# SCH_Club-Vote-Decider_2025-12-05_1.net
KiCad netlist of a schematic drawn in EasyEDA
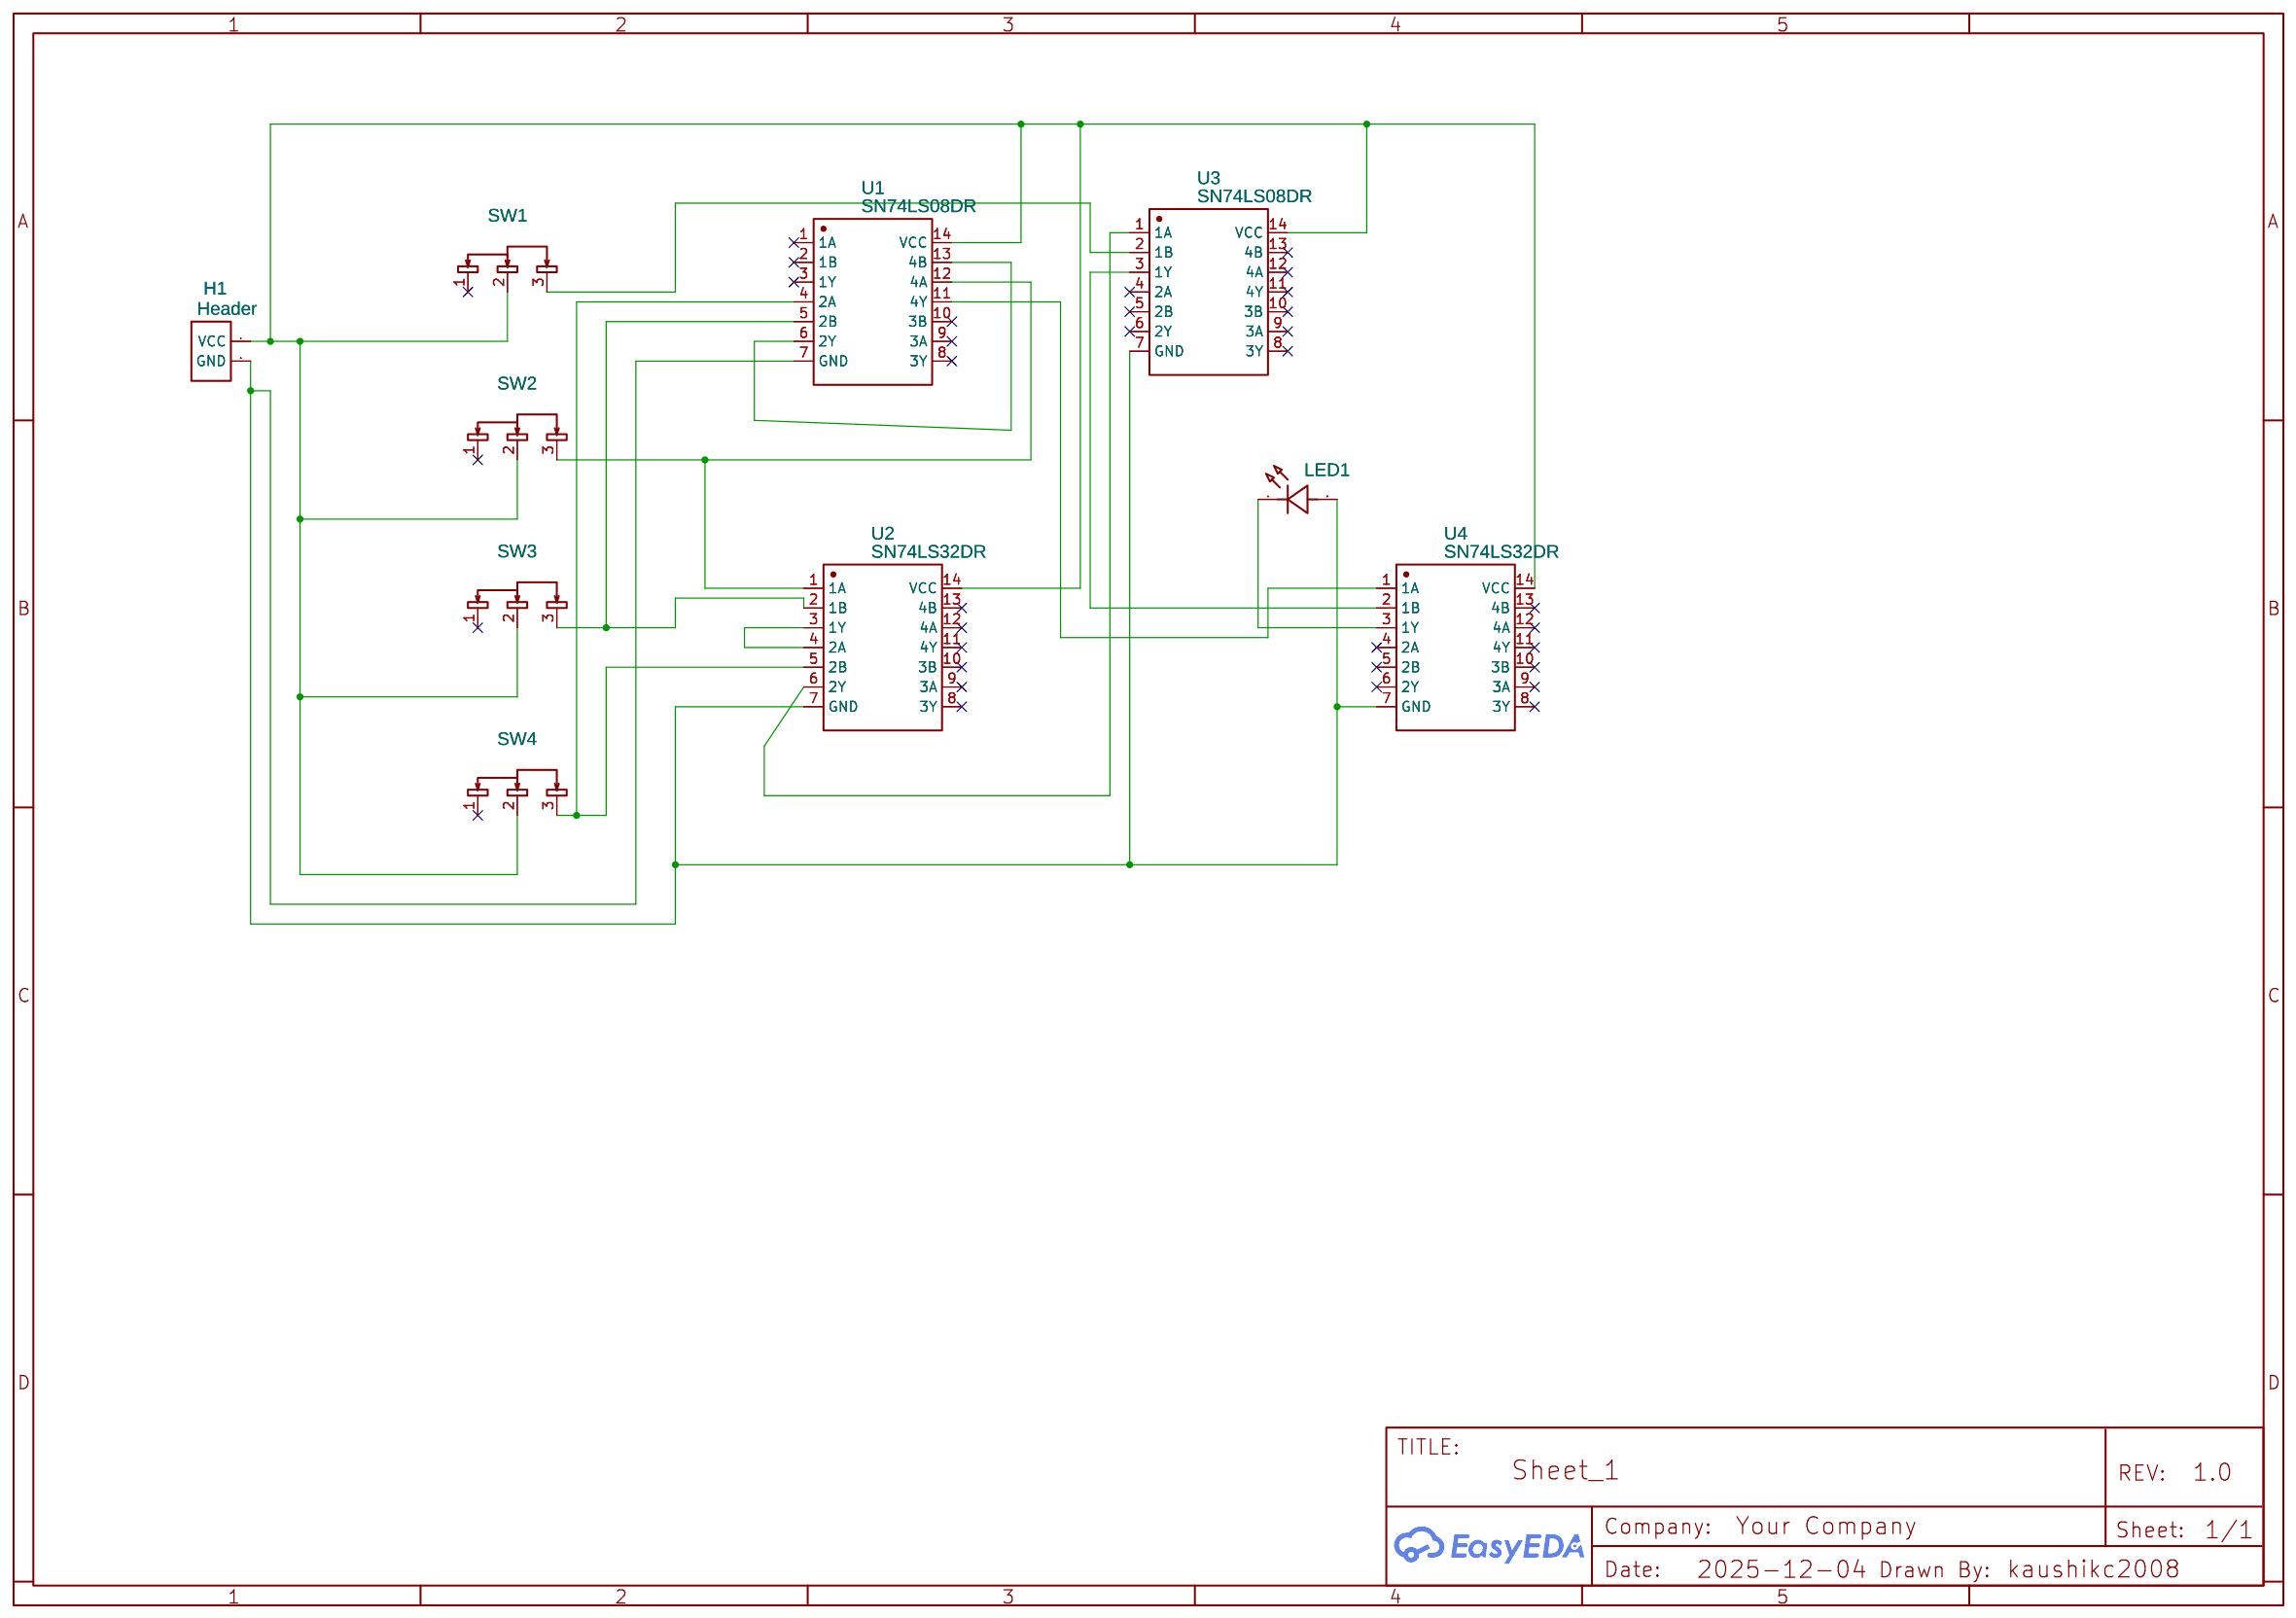
[diagram p0: schematic sheet]

(export (version "E")
  (design (tool "Eeschema 10.0.6"))
  (components
    (comp (ref "H1") (value "Header") (libsource (lib "") (part "HEADER-FEMALE-2.54_1X2")))
    (comp (ref "LED1")
      (value "XL-502UWC")
      (fields (field (name "Manufacturer") "XINGLIGHT(成兴光)"))
      (libsource (lib "") (part "XL-502UWC"))
    )
    (comp (ref "SW1")
      (value "MST-12D18G4 SPDT SLIDE SWITCH")
      (fields
        (field (name "Manufacturer Part") "MST-12D18G4 SPDT Slide Switch")
        (field (name "Manufacturer") "SHOU HAN(首韩)")
      )
      (libsource (lib "") (part "MST-12D18G4 SPDT SLIDE SWITCH"))
    )
    (comp (ref "SW2")
      (value "MST-12D18G4 SPDT SLIDE SWITCH")
      (fields
        (field (name "Manufacturer Part") "MST-12D18G4 SPDT Slide Switch")
        (field (name "Manufacturer") "SHOU HAN(首韩)")
      )
      (libsource (lib "") (part "MST-12D18G4 SPDT SLIDE SWITCH"))
    )
    (comp (ref "SW3")
      (value "MST-12D18G4 SPDT SLIDE SWITCH")
      (fields
        (field (name "Manufacturer Part") "MST-12D18G4 SPDT Slide Switch")
        (field (name "Manufacturer") "SHOU HAN(首韩)")
      )
      (libsource (lib "") (part "MST-12D18G4 SPDT SLIDE SWITCH"))
    )
    (comp (ref "SW4")
      (value "MST-12D18G4 SPDT SLIDE SWITCH")
      (fields
        (field (name "Manufacturer Part") "MST-12D18G4 SPDT Slide Switch")
        (field (name "Manufacturer") "SHOU HAN(首韩)")
      )
      (libsource (lib "") (part "MST-12D18G4 SPDT SLIDE SWITCH"))
    )
    (comp (ref "U1")
      (value "SN74LS08DR")
      (fields (field (name "Manufacturer") "TI(德州仪器)"))
      (libsource (lib "") (part "SN74LS08DR"))
    )
    (comp (ref "U2")
      (value "SN74LS32DR")
      (fields (field (name "Manufacturer") "TI(德州仪器)"))
      (libsource (lib "") (part "SN74LS32DR"))
    )
    (comp (ref "U3")
      (value "SN74LS08DR")
      (fields (field (name "Manufacturer") "TI(德州仪器)"))
      (libsource (lib "") (part "SN74LS08DR"))
    )
    (comp (ref "U4")
      (value "SN74LS32DR")
      (fields (field (name "Manufacturer") "TI(德州仪器)"))
      (libsource (lib "") (part "SN74LS32DR"))
    )
  )
  (nets
    (net (code "1") (name "Net-(H1-GND)") (class "Default")
      (node (ref "H1") (pin "2") (pinfunction "GND_2") (pintype "unspecified"))
      (node (ref "LED1") (pin "2") (pinfunction "A_2") (pintype "unspecified"))
      (node (ref "U1") (pin "7") (pinfunction "GND_7") (pintype "unspecified"))
      (node (ref "U2") (pin "7") (pinfunction "GND_7") (pintype "unspecified"))
      (node (ref "U3") (pin "7") (pinfunction "GND_7") (pintype "unspecified"))
      (node (ref "U4") (pin "7") (pinfunction "GND_7") (pintype "unspecified"))
    )
    (net (code "2") (name "Net-(H1-VCC)") (class "Default")
      (node (ref "H1") (pin "1") (pinfunction "VCC_1") (pintype "unspecified"))
      (node (ref "SW1") (pin "2") (pinfunction "2_2") (pintype "unspecified"))
      (node (ref "SW2") (pin "2") (pinfunction "2_2") (pintype "unspecified"))
      (node (ref "SW3") (pin "2") (pinfunction "2_2") (pintype "unspecified"))
      (node (ref "SW4") (pin "2") (pinfunction "2_2") (pintype "unspecified"))
      (node (ref "U1") (pin "14") (pinfunction "VCC_14") (pintype "unspecified"))
      (node (ref "U2") (pin "14") (pinfunction "VCC_14") (pintype "unspecified"))
      (node (ref "U3") (pin "14") (pinfunction "VCC_14") (pintype "unspecified"))
      (node (ref "U4") (pin "14") (pinfunction "VCC_14") (pintype "unspecified"))
    )
    (net (code "3") (name "Net-(LED1-K)") (class "Default")
      (node (ref "LED1") (pin "1") (pinfunction "K_1") (pintype "unspecified"))
      (node (ref "U4") (pin "3") (pinfunction "1Y_3") (pintype "unspecified"))
    )
    (net (code "4") (name "Net-(U1-2A)") (class "Default")
      (node (ref "SW4") (pin "3") (pinfunction "3_3") (pintype "unspecified"))
      (node (ref "U1") (pin "4") (pinfunction "2A_4") (pintype "unspecified"))
      (node (ref "U2") (pin "5") (pinfunction "2B_5") (pintype "unspecified"))
    )
    (net (code "5") (name "Net-(U1-2B)") (class "Default")
      (node (ref "SW3") (pin "3") (pinfunction "3_3") (pintype "unspecified"))
      (node (ref "U1") (pin "5") (pinfunction "2B_5") (pintype "unspecified"))
      (node (ref "U2") (pin "2") (pinfunction "1B_2") (pintype "unspecified"))
    )
    (net (code "6") (name "Net-(U1-2Y)") (class "Default")
      (node (ref "U1") (pin "13") (pinfunction "4B_13") (pintype "unspecified"))
      (node (ref "U1") (pin "6") (pinfunction "2Y_6") (pintype "unspecified"))
    )
    (net (code "7") (name "Net-(U1-4A)") (class "Default")
      (node (ref "SW2") (pin "3") (pinfunction "3_3") (pintype "unspecified"))
      (node (ref "U1") (pin "12") (pinfunction "4A_12") (pintype "unspecified"))
      (node (ref "U2") (pin "1") (pinfunction "1A_1") (pintype "unspecified"))
    )
    (net (code "8") (name "Net-(U1-4Y)") (class "Default")
      (node (ref "U1") (pin "11") (pinfunction "4Y_11") (pintype "unspecified"))
      (node (ref "U4") (pin "1") (pinfunction "1A_1") (pintype "unspecified"))
    )
    (net (code "9") (name "Net-(U2-1Y)") (class "Default")
      (node (ref "U2") (pin "3") (pinfunction "1Y_3") (pintype "unspecified"))
      (node (ref "U2") (pin "4") (pinfunction "2A_4") (pintype "unspecified"))
    )
    (net (code "10") (name "Net-(U2-2Y)") (class "Default")
      (node (ref "U2") (pin "6") (pinfunction "2Y_6") (pintype "unspecified"))
      (node (ref "U3") (pin "1") (pinfunction "1A_1") (pintype "unspecified"))
    )
    (net (code "11") (name "Net-(U3-1B)") (class "Default")
      (node (ref "SW1") (pin "3") (pinfunction "3_3") (pintype "unspecified"))
      (node (ref "U3") (pin "2") (pinfunction "1B_2") (pintype "unspecified"))
    )
    (net (code "12") (name "Net-(U3-1Y)") (class "Default")
      (node (ref "U3") (pin "3") (pinfunction "1Y_3") (pintype "unspecified"))
      (node (ref "U4") (pin "2") (pinfunction "1B_2") (pintype "unspecified"))
    )
    (net (code "13") (name "unconnected-(SW1-Pad1)") (class "Default")
      (node (ref "SW1") (pin "1") (pinfunction "1_1") (pintype "unspecified+no_connect"))
    )
    (net (code "14") (name "unconnected-(SW2-Pad1)") (class "Default")
      (node (ref "SW2") (pin "1") (pinfunction "1_1") (pintype "unspecified+no_connect"))
    )
    (net (code "15") (name "unconnected-(SW3-Pad1)") (class "Default")
      (node (ref "SW3") (pin "1") (pinfunction "1_1") (pintype "unspecified+no_connect"))
    )
    (net (code "16") (name "unconnected-(SW4-Pad1)") (class "Default")
      (node (ref "SW4") (pin "1") (pinfunction "1_1") (pintype "unspecified+no_connect"))
    )
    (net (code "17") (name "unconnected-(U1-1A-Pad1)") (class "Default")
      (node (ref "U1") (pin "1") (pinfunction "1A_1") (pintype "unspecified+no_connect"))
    )
    (net (code "18") (name "unconnected-(U1-1B-Pad2)") (class "Default")
      (node (ref "U1") (pin "2") (pinfunction "1B_2") (pintype "unspecified+no_connect"))
    )
    (net (code "19") (name "unconnected-(U1-1Y-Pad3)") (class "Default")
      (node (ref "U1") (pin "3") (pinfunction "1Y_3") (pintype "unspecified+no_connect"))
    )
    (net (code "20") (name "unconnected-(U1-3A-Pad9)") (class "Default")
      (node (ref "U1") (pin "9") (pinfunction "3A_9") (pintype "unspecified+no_connect"))
    )
    (net (code "21") (name "unconnected-(U1-3B-Pad10)") (class "Default")
      (node (ref "U1") (pin "10") (pinfunction "3B_10") (pintype "unspecified+no_connect"))
    )
    (net (code "22") (name "unconnected-(U1-3Y-Pad8)") (class "Default")
      (node (ref "U1") (pin "8") (pinfunction "3Y_8") (pintype "unspecified+no_connect"))
    )
    (net (code "23") (name "unconnected-(U2-3A-Pad9)") (class "Default")
      (node (ref "U2") (pin "9") (pinfunction "3A_9") (pintype "unspecified+no_connect"))
    )
    (net (code "24") (name "unconnected-(U2-3B-Pad10)") (class "Default")
      (node (ref "U2") (pin "10") (pinfunction "3B_10") (pintype "unspecified+no_connect"))
    )
    (net (code "25") (name "unconnected-(U2-3Y-Pad8)") (class "Default")
      (node (ref "U2") (pin "8") (pinfunction "3Y_8") (pintype "unspecified+no_connect"))
    )
    (net (code "26") (name "unconnected-(U2-4A-Pad12)") (class "Default")
      (node (ref "U2") (pin "12") (pinfunction "4A_12") (pintype "unspecified+no_connect"))
    )
    (net (code "27") (name "unconnected-(U2-4B-Pad13)") (class "Default")
      (node (ref "U2") (pin "13") (pinfunction "4B_13") (pintype "unspecified+no_connect"))
    )
    (net (code "28") (name "unconnected-(U2-4Y-Pad11)") (class "Default")
      (node (ref "U2") (pin "11") (pinfunction "4Y_11") (pintype "unspecified+no_connect"))
    )
    (net (code "29") (name "unconnected-(U3-2A-Pad4)") (class "Default")
      (node (ref "U3") (pin "4") (pinfunction "2A_4") (pintype "unspecified+no_connect"))
    )
    (net (code "30") (name "unconnected-(U3-2B-Pad5)") (class "Default")
      (node (ref "U3") (pin "5") (pinfunction "2B_5") (pintype "unspecified+no_connect"))
    )
    (net (code "31") (name "unconnected-(U3-2Y-Pad6)") (class "Default")
      (node (ref "U3") (pin "6") (pinfunction "2Y_6") (pintype "unspecified+no_connect"))
    )
    (net (code "32") (name "unconnected-(U3-3A-Pad9)") (class "Default")
      (node (ref "U3") (pin "9") (pinfunction "3A_9") (pintype "unspecified+no_connect"))
    )
    (net (code "33") (name "unconnected-(U3-3B-Pad10)") (class "Default")
      (node (ref "U3") (pin "10") (pinfunction "3B_10") (pintype "unspecified+no_connect"))
    )
    (net (code "34") (name "unconnected-(U3-3Y-Pad8)") (class "Default")
      (node (ref "U3") (pin "8") (pinfunction "3Y_8") (pintype "unspecified+no_connect"))
    )
    (net (code "35") (name "unconnected-(U3-4A-Pad12)") (class "Default")
      (node (ref "U3") (pin "12") (pinfunction "4A_12") (pintype "unspecified+no_connect"))
    )
    (net (code "36") (name "unconnected-(U3-4B-Pad13)") (class "Default")
      (node (ref "U3") (pin "13") (pinfunction "4B_13") (pintype "unspecified+no_connect"))
    )
    (net (code "37") (name "unconnected-(U3-4Y-Pad11)") (class "Default")
      (node (ref "U3") (pin "11") (pinfunction "4Y_11") (pintype "unspecified+no_connect"))
    )
    (net (code "38") (name "unconnected-(U4-2A-Pad4)") (class "Default")
      (node (ref "U4") (pin "4") (pinfunction "2A_4") (pintype "unspecified+no_connect"))
    )
    (net (code "39") (name "unconnected-(U4-2B-Pad5)") (class "Default")
      (node (ref "U4") (pin "5") (pinfunction "2B_5") (pintype "unspecified+no_connect"))
    )
    (net (code "40") (name "unconnected-(U4-2Y-Pad6)") (class "Default")
      (node (ref "U4") (pin "6") (pinfunction "2Y_6") (pintype "unspecified+no_connect"))
    )
    (net (code "41") (name "unconnected-(U4-3A-Pad9)") (class "Default")
      (node (ref "U4") (pin "9") (pinfunction "3A_9") (pintype "unspecified+no_connect"))
    )
    (net (code "42") (name "unconnected-(U4-3B-Pad10)") (class "Default")
      (node (ref "U4") (pin "10") (pinfunction "3B_10") (pintype "unspecified+no_connect"))
    )
    (net (code "43") (name "unconnected-(U4-3Y-Pad8)") (class "Default")
      (node (ref "U4") (pin "8") (pinfunction "3Y_8") (pintype "unspecified+no_connect"))
    )
    (net (code "44") (name "unconnected-(U4-4A-Pad12)") (class "Default")
      (node (ref "U4") (pin "12") (pinfunction "4A_12") (pintype "unspecified+no_connect"))
    )
    (net (code "45") (name "unconnected-(U4-4B-Pad13)") (class "Default")
      (node (ref "U4") (pin "13") (pinfunction "4B_13") (pintype "unspecified+no_connect"))
    )
    (net (code "46") (name "unconnected-(U4-4Y-Pad11)") (class "Default")
      (node (ref "U4") (pin "11") (pinfunction "4Y_11") (pintype "unspecified+no_connect"))
    )
  )
)
